# ModulePlatform.net
KiCad netlist of a schematic drawn in EAGLE
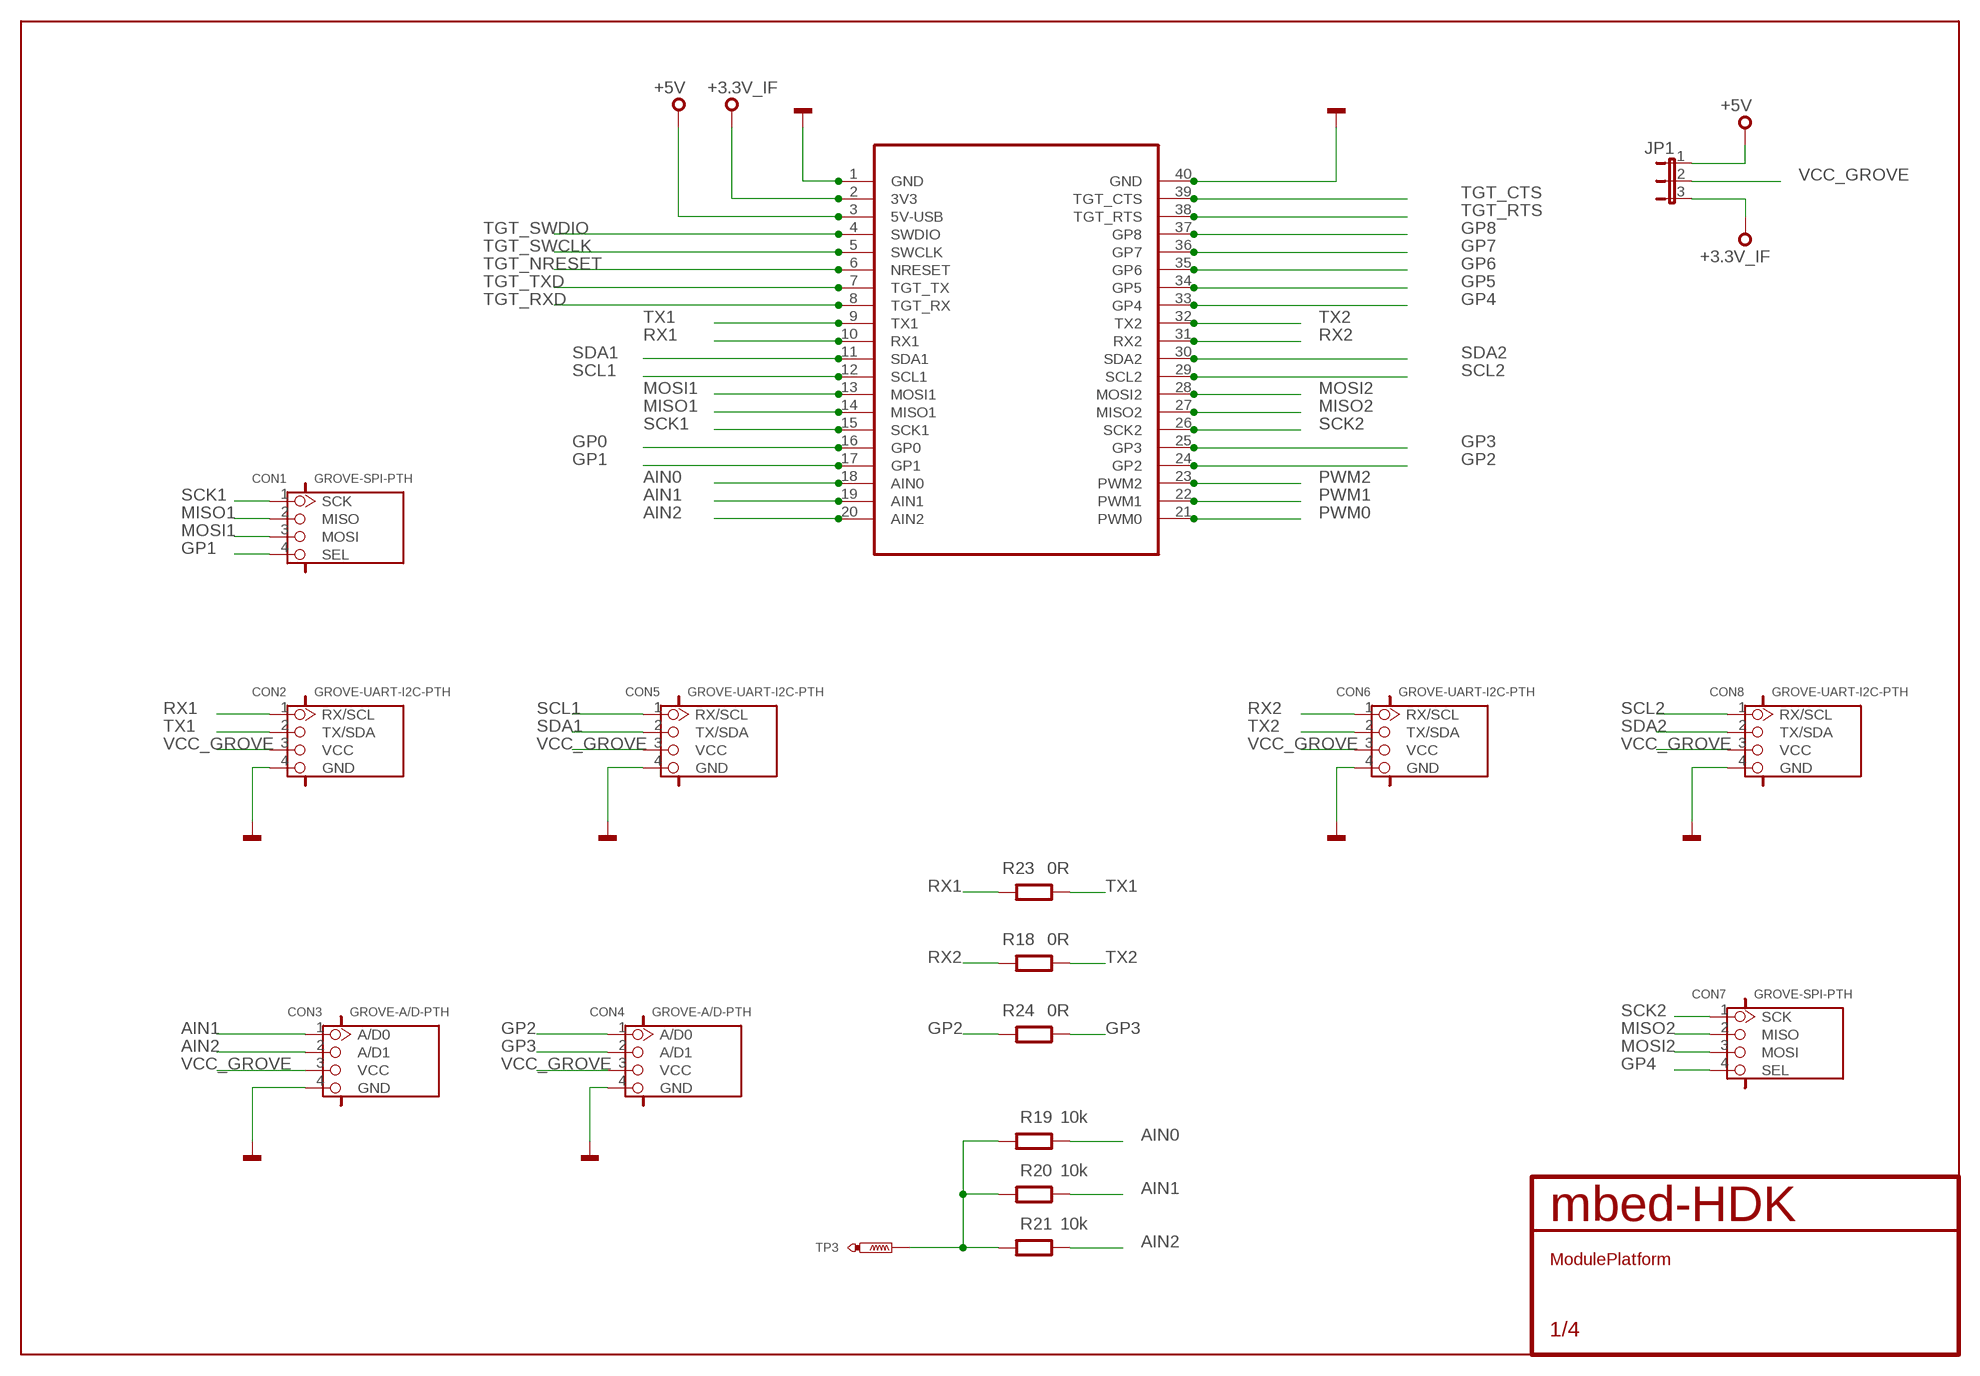
[diagram p0: schematic, sheet 1]
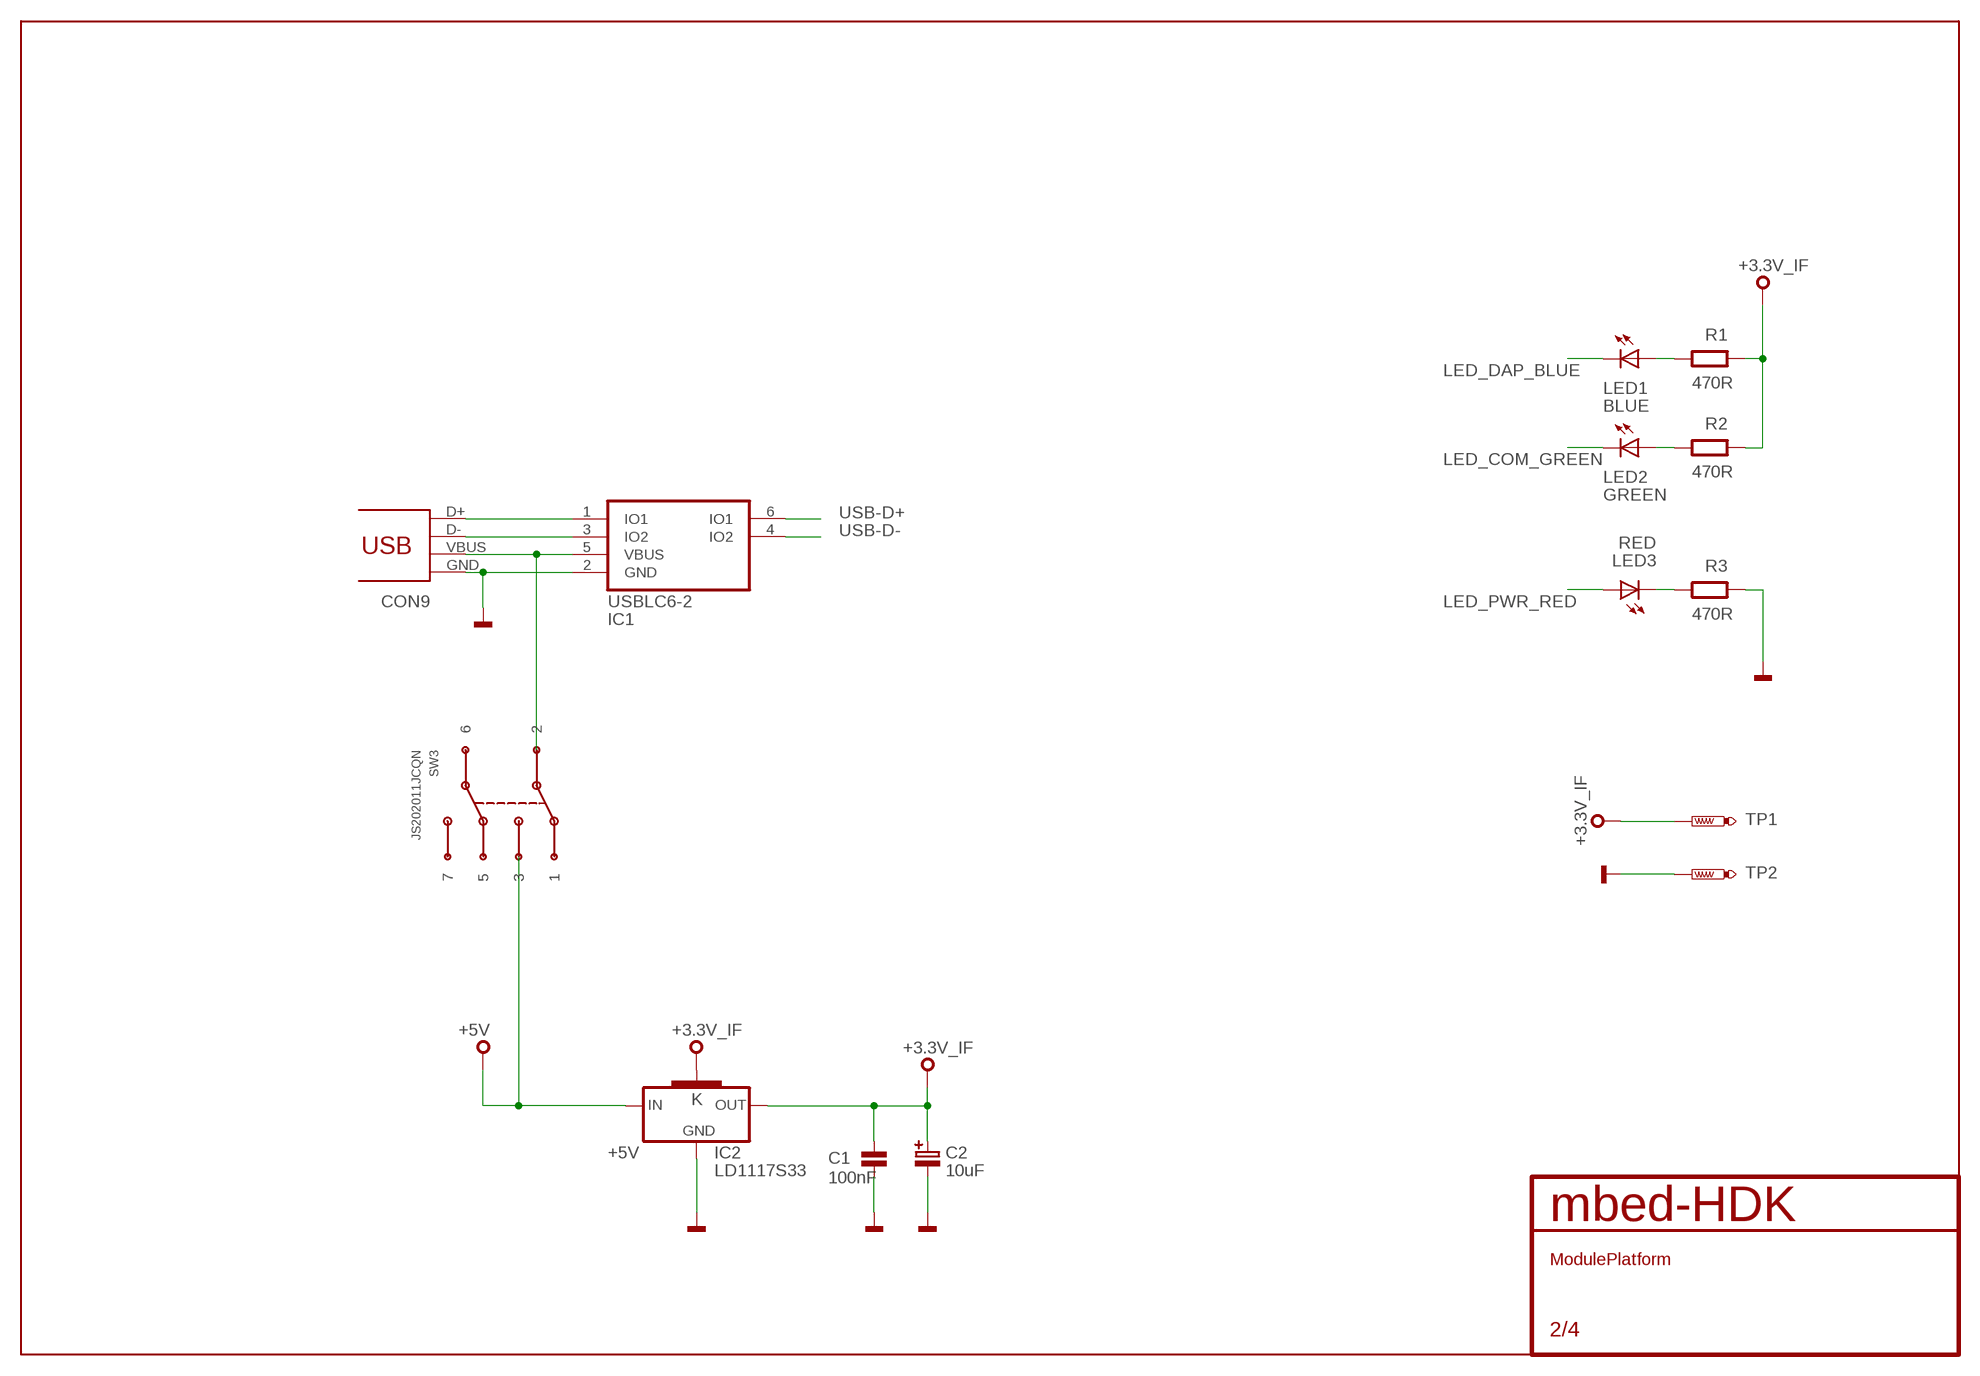
[diagram p1: schematic, sheet 2]
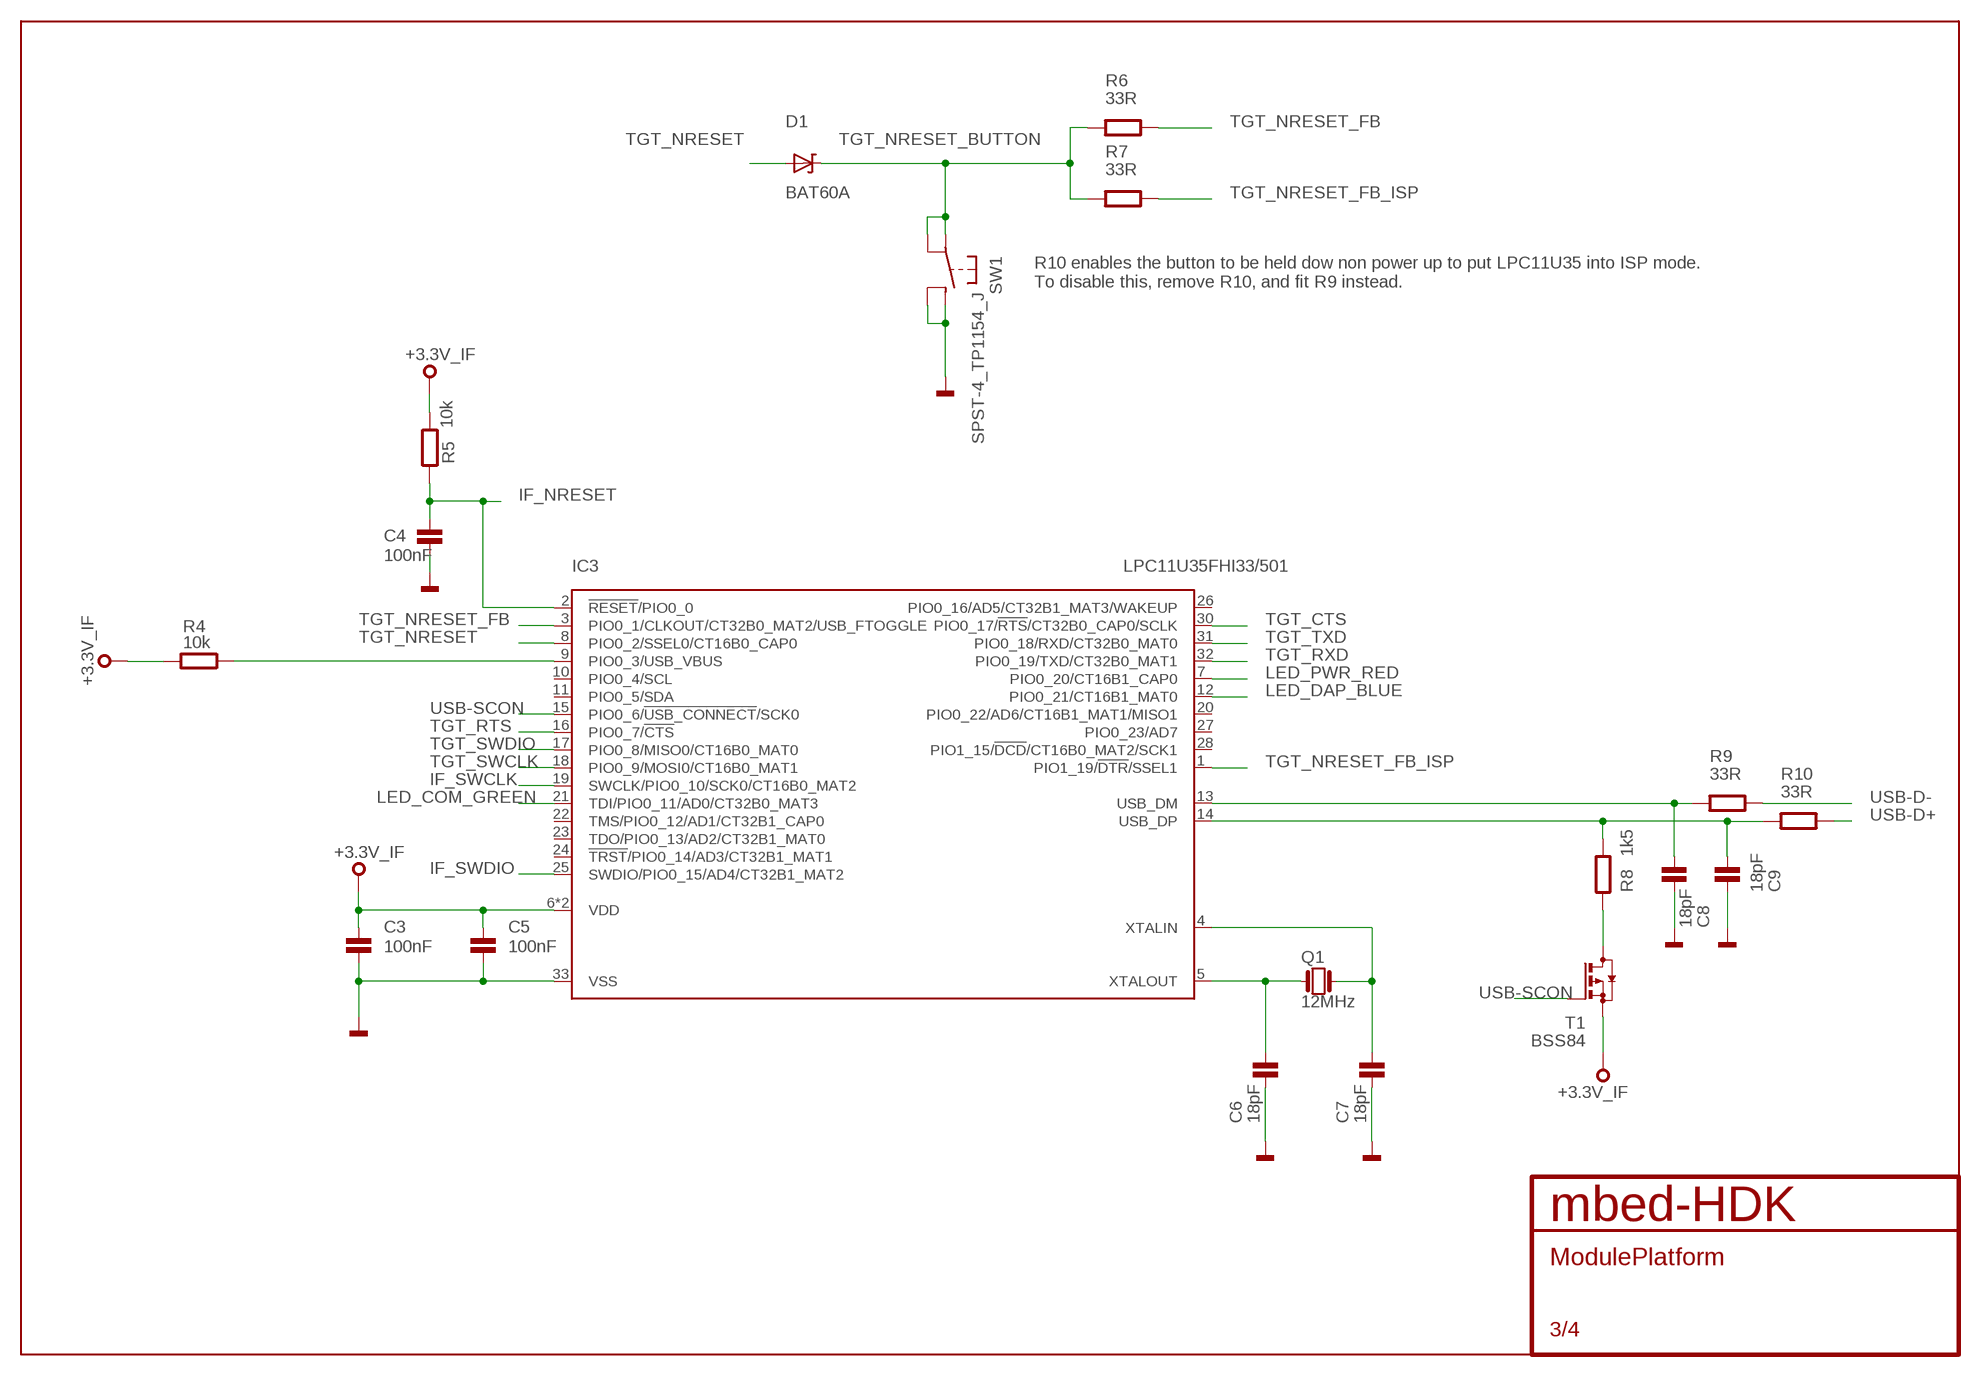
[diagram p2: schematic, sheet 3]
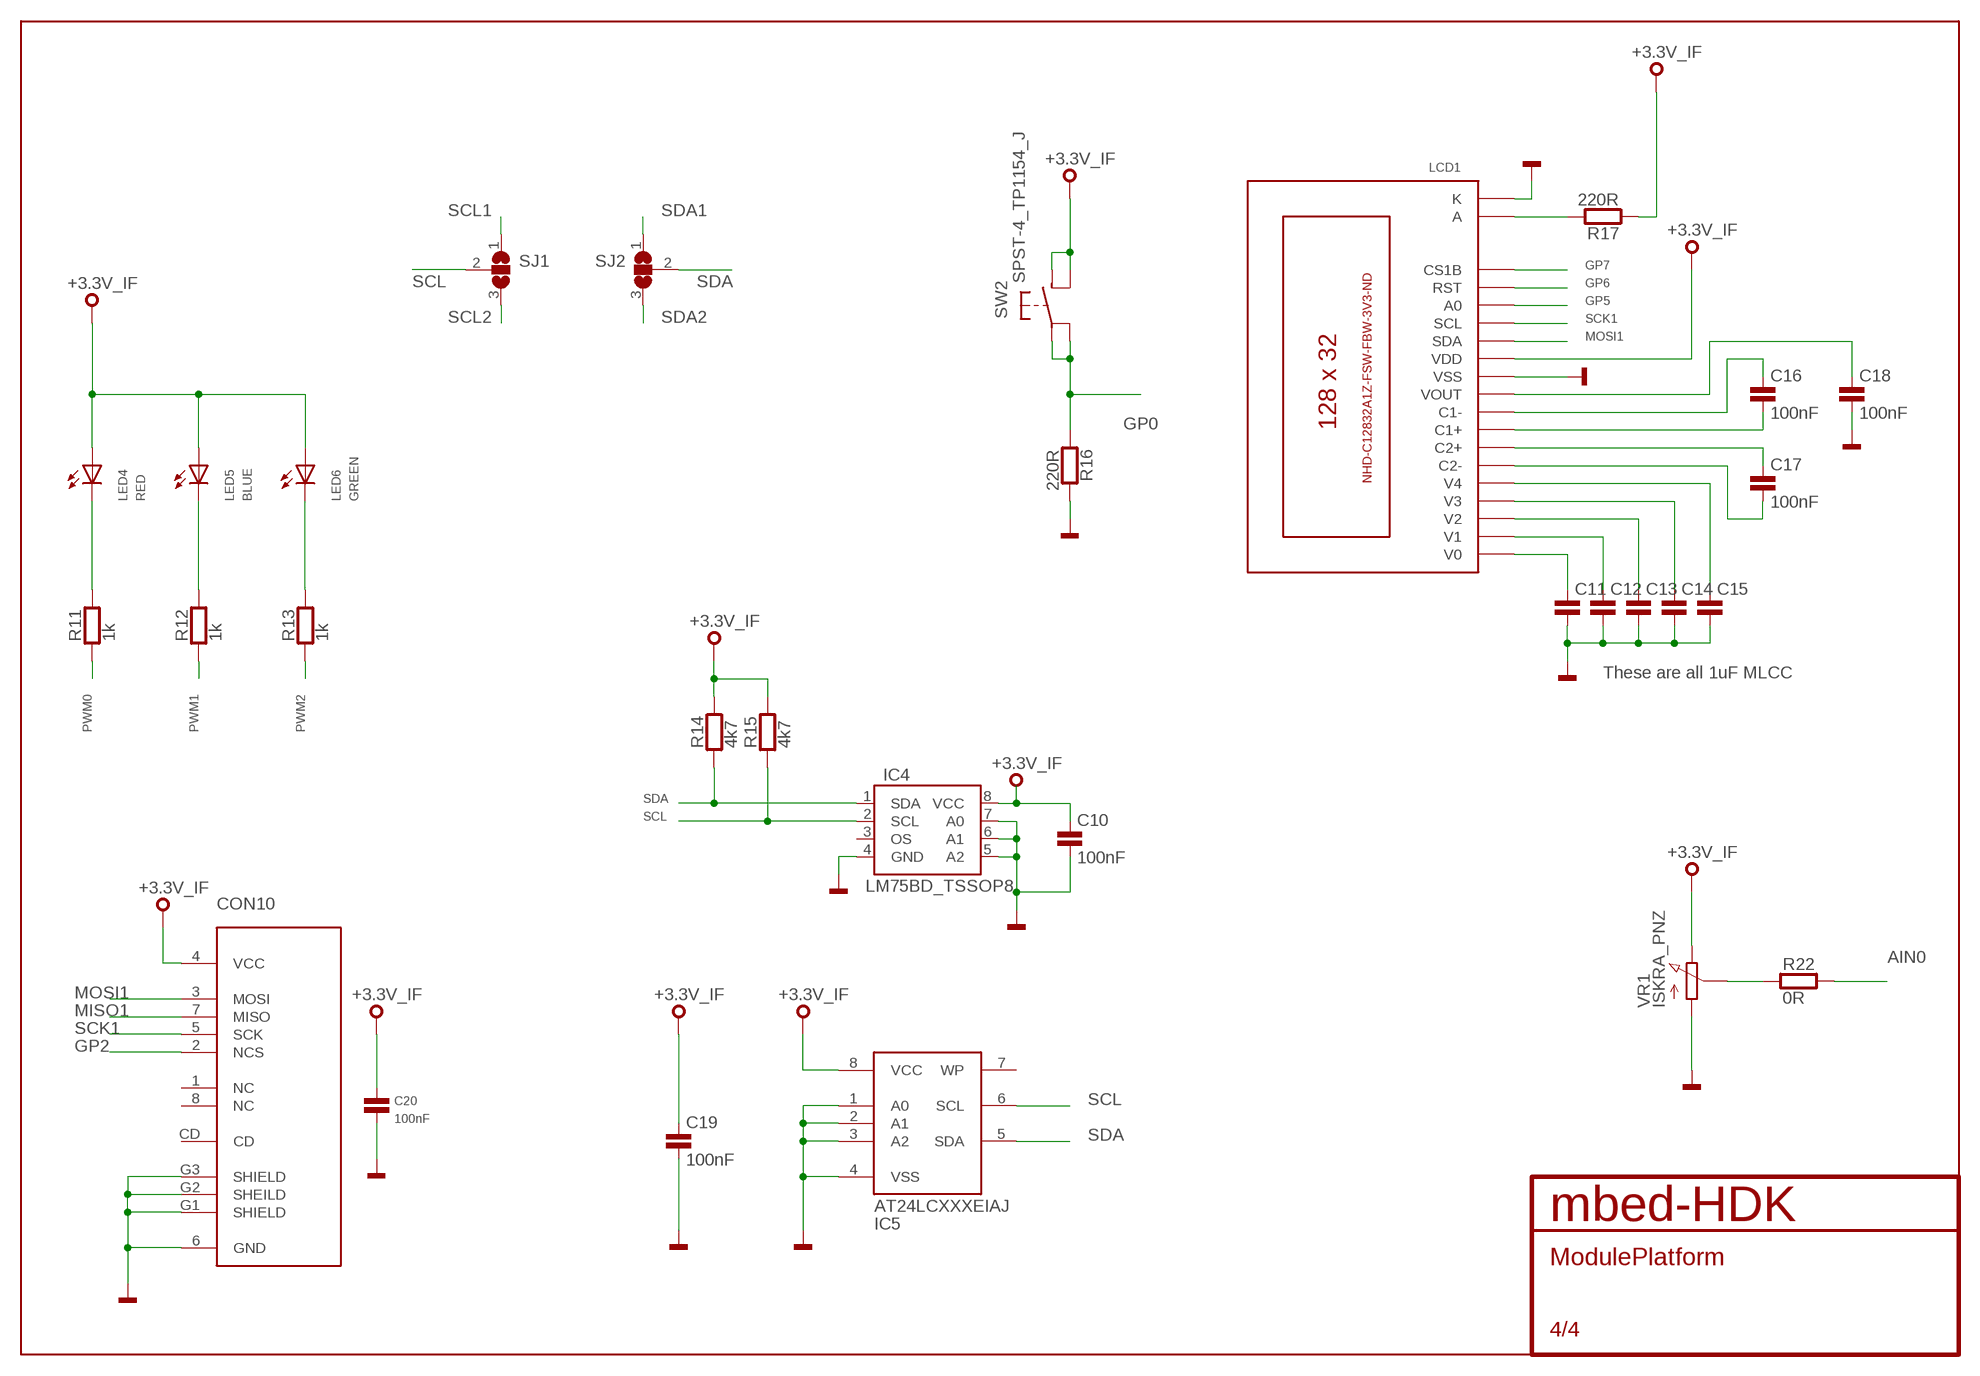
[diagram p3: schematic, sheet 4]

(export (version "E")
  (design (tool "Eeschema 10.0.6"))
  (components
    (comp (ref "C10")
      (value "100nF")
      (footprint "eagle-import:0603")
      (libsource (lib "eagle-import") (part "mbed-rlcq_C0603"))
    )
    (comp (ref "C11")
      (value "100nF")
      (footprint "eagle-import:0603")
      (libsource (lib "eagle-import") (part "mbed-rlcq_C0603"))
    )
    (comp (ref "C12")
      (value "100nF")
      (footprint "eagle-import:0603")
      (libsource (lib "eagle-import") (part "mbed-rlcq_C0603"))
    )
    (comp (ref "C13")
      (value "100nF")
      (footprint "eagle-import:0603")
      (libsource (lib "eagle-import") (part "mbed-rlcq_C0603"))
    )
    (comp (ref "C14")
      (value "100nF")
      (footprint "eagle-import:0603")
      (libsource (lib "eagle-import") (part "mbed-rlcq_C0603"))
    )
    (comp (ref "C15")
      (value "100nF")
      (footprint "eagle-import:0603")
      (libsource (lib "eagle-import") (part "mbed-rlcq_C0603"))
    )
    (comp (ref "C16")
      (value "100nF")
      (footprint "eagle-import:0603")
      (libsource (lib "eagle-import") (part "mbed-rlcq_C0603"))
    )
    (comp (ref "C17")
      (value "100nF")
      (footprint "eagle-import:0603")
      (libsource (lib "eagle-import") (part "mbed-rlcq_C0603"))
    )
    (comp (ref "C18")
      (value "100nF")
      (footprint "eagle-import:0603")
      (libsource (lib "eagle-import") (part "mbed-rlcq_C0603"))
    )
    (comp (ref "C19")
      (value "100nF")
      (footprint "eagle-import:0603")
      (libsource (lib "eagle-import") (part "mbed-rlcq_C0603"))
    )
    (comp (ref "C20")
      (value "100nF")
      (footprint "eagle-import:0603")
      (libsource (lib "eagle-import") (part "C0603"))
    )
    (comp (ref "CON10")
      (value "MICRO-SD")
      (footprint "eagle-import:AMPHENOL-101-00660-68-6")
      (libsource (lib "eagle-import") (part "MICRO-SD"))
    )
    (comp (ref "IC4")
      (value "LM75BD_TSSOP8")
      (footprint "eagle-import:TSSOP8")
      (libsource (lib "eagle-import") (part "LM75BD_TSSOP8"))
    )
    (comp (ref "IC5")
      (value "AT24LCXXXEIAJ")
      (footprint "eagle-import:SO08-EIAJ")
      (libsource (lib "eagle-import") (part "AT24LCXXXEIAJ"))
    )
    (comp (ref "LCD1")
      (value "C12832A1Z")
      (footprint "eagle-import:C12832A1Z")
      (libsource (lib "eagle-import") (part "C12832A1Z"))
    )
    (comp (ref "LED4")
      (value "RED")
      (footprint "eagle-import:CHIPLED_0603")
      (libsource (lib "eagle-import") (part "LED0603"))
    )
    (comp (ref "LED5")
      (value "BLUE")
      (footprint "eagle-import:CHIPLED_0603")
      (libsource (lib "eagle-import") (part "LED0603"))
    )
    (comp (ref "LED6")
      (value "GREEN")
      (footprint "eagle-import:CHIPLED_0603")
      (libsource (lib "eagle-import") (part "LED0603"))
    )
    (comp (ref "R11")
      (value "1k")
      (footprint "eagle-import:0603")
      (libsource (lib "eagle-import") (part "mbed-rlcq_R0603"))
    )
    (comp (ref "R12")
      (value "1k")
      (footprint "eagle-import:0603")
      (libsource (lib "eagle-import") (part "mbed-rlcq_R0603"))
    )
    (comp (ref "R13")
      (value "1k")
      (footprint "eagle-import:0603")
      (libsource (lib "eagle-import") (part "mbed-rlcq_R0603"))
    )
    (comp (ref "R14")
      (value "4k7")
      (footprint "eagle-import:0603")
      (libsource (lib "eagle-import") (part "mbed-rlcq_R0603"))
    )
    (comp (ref "R15")
      (value "4k7")
      (footprint "eagle-import:0603")
      (libsource (lib "eagle-import") (part "mbed-rlcq_R0603"))
    )
    (comp (ref "R16")
      (value "220R")
      (footprint "eagle-import:0603")
      (libsource (lib "eagle-import") (part "mbed-rlcq_R0603"))
    )
    (comp (ref "R17")
      (value "220R")
      (footprint "eagle-import:0603")
      (libsource (lib "eagle-import") (part "mbed-rlcq_R0603"))
    )
    (comp (ref "R22")
      (value "0R")
      (footprint "eagle-import:0603")
      (libsource (lib "eagle-import") (part "mbed-rlcq_R0603"))
    )
    (comp (ref "SJ1")
      (value "SJ2W")
      (footprint "eagle-import:SJ_2")
      (libsource (lib "eagle-import") (part "SJ2W"))
    )
    (comp (ref "SJ2")
      (value "SJ2W")
      (footprint "eagle-import:SJ_2")
      (libsource (lib "eagle-import") (part "SJ2W"))
    )
    (comp (ref "SW2")
      (value "SPST-4_TP1154_J")
      (footprint "eagle-import:TP-1154X")
      (libsource (lib "eagle-import") (part "SPST-4_TP1154_J"))
    )
    (comp (ref "VR1")
      (value "ISKRA_PNZ")
      (footprint "eagle-import:CA14V")
      (libsource (lib "eagle-import") (part "ISKRA_PNZ"))
    )
    (comp (ref "C3")
      (value "100nF")
      (footprint "eagle-import:0603")
      (libsource (lib "eagle-import") (part "C0603"))
    )
    (comp (ref "C4")
      (value "100nF")
      (footprint "eagle-import:0603")
      (libsource (lib "eagle-import") (part "C0603"))
    )
    (comp (ref "C5")
      (value "100nF")
      (footprint "eagle-import:0603")
      (libsource (lib "eagle-import") (part "C0603"))
    )
    (comp (ref "C6")
      (value "18pF")
      (footprint "eagle-import:0603")
      (libsource (lib "eagle-import") (part "C0603"))
    )
    (comp (ref "C7")
      (value "18pF")
      (footprint "eagle-import:0603")
      (libsource (lib "eagle-import") (part "C0603"))
    )
    (comp (ref "C8")
      (value "18pF")
      (footprint "eagle-import:0603")
      (libsource (lib "eagle-import") (part "C0603"))
    )
    (comp (ref "C9")
      (value "18pF")
      (footprint "eagle-import:0603")
      (libsource (lib "eagle-import") (part "C0603"))
    )
    (comp (ref "D1")
      (value "BAT60A")
      (footprint "eagle-import:BAT60A")
      (libsource (lib "eagle-import") (part "BAT60A"))
    )
    (comp (ref "IC3")
      (value "LPC11U35FHI33/501")
      (footprint "eagle-import:SOT617-3")
      (libsource (lib "eagle-import") (part "LPC11U35FHI33/501"))
    )
    (comp (ref "Q1")
      (value "12MHz")
      (footprint "eagle-import:3.2X.2.5")
      (libsource (lib "eagle-import") (part "Q_3.2X2.5"))
    )
    (comp (ref "R4")
      (value "10k")
      (footprint "eagle-import:0603@1")
      (libsource (lib "eagle-import") (part "R0603"))
    )
    (comp (ref "R5")
      (value "10k")
      (footprint "eagle-import:0603@1")
      (libsource (lib "eagle-import") (part "R0603"))
    )
    (comp (ref "R6")
      (value "33R")
      (footprint "eagle-import:0603@1")
      (libsource (lib "eagle-import") (part "R0603"))
    )
    (comp (ref "R7")
      (value "33R")
      (footprint "eagle-import:0603@1")
      (libsource (lib "eagle-import") (part "R0603"))
    )
    (comp (ref "R8")
      (value "1k5")
      (footprint "eagle-import:0603@1")
      (libsource (lib "eagle-import") (part "R0603"))
    )
    (comp (ref "R9")
      (value "33R")
      (footprint "eagle-import:0603@1")
      (libsource (lib "eagle-import") (part "R0603"))
    )
    (comp (ref "R10")
      (value "33R")
      (footprint "eagle-import:0603@1")
      (libsource (lib "eagle-import") (part "R0603"))
    )
    (comp (ref "SW1")
      (value "SPST-4_TP1154_J")
      (footprint "eagle-import:TP-1154X")
      (libsource (lib "eagle-import") (part "SPST-4_TP1154_J"))
    )
    (comp (ref "T1")
      (value "BSS84")
      (footprint "eagle-import:SOT23")
      (libsource (lib "eagle-import") (part "BSS84"))
    )
    (comp (ref "CON1")
      (value "GROVE-SPI-PTH")
      (footprint "eagle-import:HW4-2.0")
      (libsource (lib "eagle-import") (part "GROVE-SPI-PTH"))
    )
    (comp (ref "CON2")
      (value "GROVE-UART-I2C-PTH")
      (footprint "eagle-import:HW4-2.0")
      (libsource (lib "eagle-import") (part "GROVE-UART-I2C-PTH"))
    )
    (comp (ref "CON3")
      (value "GROVE-A/D-PTH")
      (footprint "eagle-import:HW4-2.0")
      (libsource (lib "eagle-import") (part "GROVE-A/D-PTH"))
    )
    (comp (ref "CON4")
      (value "GROVE-A/D-PTH")
      (footprint "eagle-import:HW4-2.0")
      (libsource (lib "eagle-import") (part "GROVE-A/D-PTH"))
    )
    (comp (ref "CON5")
      (value "GROVE-UART-I2C-PTH")
      (footprint "eagle-import:HW4-2.0")
      (libsource (lib "eagle-import") (part "GROVE-UART-I2C-PTH"))
    )
    (comp (ref "CON6")
      (value "GROVE-UART-I2C-PTH")
      (footprint "eagle-import:HW4-2.0")
      (libsource (lib "eagle-import") (part "GROVE-UART-I2C-PTH"))
    )
    (comp (ref "CON7")
      (value "GROVE-SPI-PTH")
      (footprint "eagle-import:HW4-2.0")
      (libsource (lib "eagle-import") (part "GROVE-SPI-PTH"))
    )
    (comp (ref "CON8")
      (value "GROVE-UART-I2C-PTH")
      (footprint "eagle-import:HW4-2.0")
      (libsource (lib "eagle-import") (part "GROVE-UART-I2C-PTH"))
    )
    (comp (ref "JP1")
      (value "JP2E")
      (footprint "eagle-import:JP2")
      (libsource (lib "eagle-import") (part "JP2E"))
    )
    (comp (ref "R18")
      (value "0R")
      (footprint "eagle-import:0603@1")
      (libsource (lib "eagle-import") (part "R0603"))
    )
    (comp (ref "R19")
      (value "10k")
      (footprint "eagle-import:0603@1")
      (libsource (lib "eagle-import") (part "R0603"))
    )
    (comp (ref "R20")
      (value "10k")
      (footprint "eagle-import:0603@1")
      (libsource (lib "eagle-import") (part "R0603"))
    )
    (comp (ref "R21")
      (value "10k")
      (footprint "eagle-import:0603@1")
      (libsource (lib "eagle-import") (part "R0603"))
    )
    (comp (ref "R23")
      (value "0R")
      (footprint "eagle-import:0603@1")
      (libsource (lib "eagle-import") (part "R0603"))
    )
    (comp (ref "R24")
      (value "0R")
      (footprint "eagle-import:0603@1")
      (libsource (lib "eagle-import") (part "R0603"))
    )
    (comp (ref "SKT1")
      (value "MODULE_SOCKET")
      (footprint "eagle-import:MODULE_SOCKET")
      (libsource (lib "eagle-import") (part "MODULE_SOCKET"))
    )
    (comp (ref "TP3")
      (value "TEST-POINT-50R-PTH")
      (footprint "eagle-import:TP50-PTH")
      (libsource (lib "eagle-import") (part "TEST-POINT-50R-PTH"))
    )
    (comp (ref "C1")
      (value "100nF")
      (footprint "eagle-import:0603")
      (libsource (lib "eagle-import") (part "C0603"))
    )
    (comp (ref "C2")
      (value "10uF")
      (footprint "eagle-import:SMC_B")
      (libsource (lib "eagle-import") (part "C-POLB"))
    )
    (comp (ref "CON9")
      (value "USB_MICROB")
      (footprint "eagle-import:MOLEX-47364-0001")
      (libsource (lib "eagle-import") (part "USB_MICROB"))
    )
    (comp (ref "IC1")
      (value "USBLC6-2SC6")
      (footprint "eagle-import:SOT23-6L")
      (libsource (lib "eagle-import") (part "USBLC6-2SC6"))
    )
    (comp (ref "IC2")
      (value "LD1117S33")
      (footprint "eagle-import:SOT223")
      (libsource (lib "eagle-import") (part "LD1117S33"))
    )
    (comp (ref "LED1")
      (value "BLUE")
      (footprint "eagle-import:CHIPLED_0603")
      (libsource (lib "eagle-import") (part "LED0603"))
    )
    (comp (ref "LED2")
      (value "GREEN")
      (footprint "eagle-import:CHIPLED_0603")
      (libsource (lib "eagle-import") (part "LED0603"))
    )
    (comp (ref "LED3")
      (value "RED")
      (footprint "eagle-import:CHIPLED_0603")
      (libsource (lib "eagle-import") (part "LED0603"))
    )
    (comp (ref "R1")
      (value "470R")
      (footprint "eagle-import:0603@1")
      (libsource (lib "eagle-import") (part "R0603"))
    )
    (comp (ref "R2")
      (value "470R")
      (footprint "eagle-import:0603@1")
      (libsource (lib "eagle-import") (part "R0603"))
    )
    (comp (ref "R3")
      (value "470R")
      (footprint "eagle-import:0603@1")
      (libsource (lib "eagle-import") (part "R0603"))
    )
    (comp (ref "SW3")
      (value "JS202011JCQN")
      (footprint "eagle-import:JS202011JCQN")
      (fields (field (name "MF") "C&K Components"))
      (libsource (lib "eagle-import") (part "JS202011JCQN"))
    )
    (comp (ref "TP1")
      (value "TEST-POINT-50R-PTH")
      (footprint "eagle-import:TP50-PTH")
      (libsource (lib "eagle-import") (part "TEST-POINT-50R-PTH"))
    )
    (comp (ref "TP2")
      (value "TEST-POINT-50R-PTH")
      (footprint "eagle-import:TP50-PTH")
      (libsource (lib "eagle-import") (part "TEST-POINT-50R-PTH"))
    )
  )
  (nets
    (net (code "1") (name "+3.3V_IF") (class "Default")
      (node (ref "C1") (pin "1") (pinfunction "P$1_1") (pintype "passive"))
      (node (ref "C10") (pin "1") (pinfunction "P$1_1") (pintype "passive"))
      (node (ref "C19") (pin "1") (pinfunction "P$1_1") (pintype "passive"))
      (node (ref "C2") (pin "+") (pinfunction "+_+") (pintype "passive"))
      (node (ref "C20") (pin "1") (pinfunction "P$1_1") (pintype "passive"))
      (node (ref "C3") (pin "1") (pinfunction "P$1_1") (pintype "passive"))
      (node (ref "C5") (pin "1") (pinfunction "P$1_1") (pintype "passive"))
      (node (ref "CON10") (pin "4") (pinfunction "VCC_4") (pintype "bidirectional"))
      (node (ref "IC2") (pin "2") (pinfunction "OUT_2") (pintype "passive"))
      (node (ref "IC2") (pin "4") (pinfunction "K_4") (pintype "passive"))
      (node (ref "IC3") (pin "29") (pinfunction "VDD_29") (pintype "passive"))
      (node (ref "IC3") (pin "6") (pinfunction "VDD_6") (pintype "passive"))
      (node (ref "IC4") (pin "8") (pinfunction "VCC_8") (pintype "bidirectional"))
      (node (ref "IC5") (pin "8") (pinfunction "VCC_8") (pintype "power_in"))
      (node (ref "JP1") (pin "3") (pinfunction "3_3") (pintype "passive"))
      (node (ref "LCD1") (pin "P$12") (pinfunction "VDD_P$12") (pintype "bidirectional"))
      (node (ref "LED4") (pin "A") (pinfunction "A_A") (pintype "passive"))
      (node (ref "LED5") (pin "A") (pinfunction "A_A") (pintype "passive"))
      (node (ref "LED6") (pin "A") (pinfunction "A_A") (pintype "passive"))
      (node (ref "R1") (pin "1") (pinfunction "P$1_1") (pintype "passive"))
      (node (ref "R14") (pin "2") (pinfunction "P$2_2") (pintype "passive"))
      (node (ref "R15") (pin "2") (pinfunction "P$2_2") (pintype "passive"))
      (node (ref "R17") (pin "1") (pinfunction "P$1_1") (pintype "passive"))
      (node (ref "R2") (pin "1") (pinfunction "P$1_1") (pintype "passive"))
      (node (ref "R4") (pin "2") (pinfunction "P$2_2") (pintype "passive"))
      (node (ref "R5") (pin "2") (pinfunction "P$2_2") (pintype "passive"))
      (node (ref "SKT1") (pin "2") (pinfunction "3V3_2") (pintype "bidirectional"))
      (node (ref "SKT1") (pin "P$42") (pinfunction "P$42_P$42") (pintype "bidirectional"))
      (node (ref "SW2") (pin "B1") (pinfunction "B1_B1") (pintype "passive"))
      (node (ref "SW2") (pin "B2") (pinfunction "B2_B2") (pintype "passive"))
      (node (ref "T1") (pin "2") (pinfunction "S_2") (pintype "passive"))
      (node (ref "TP1") (pin "TP") (pinfunction "TP_TP") (pintype "input"))
      (node (ref "VR1") (pin "P$3") (pinfunction "E_P$3") (pintype "passive"))
    )
    (net (code "2") (name "+5V") (class "Default")
      (node (ref "IC2") (pin "3") (pinfunction "IN_3") (pintype "input"))
      (node (ref "JP1") (pin "1") (pinfunction "1_1") (pintype "passive"))
      (node (ref "SKT1") (pin "3") (pinfunction "5V-USB_3") (pintype "bidirectional"))
      (node (ref "SKT1") (pin "P$43") (pinfunction "P$43_P$43") (pintype "bidirectional"))
      (node (ref "SW3") (pin "3") (pinfunction "3_3") (pintype "bidirectional"))
    )
    (net (code "3") (name "AIN0") (class "Default")
      (node (ref "R19") (pin "1") (pinfunction "P$1_1") (pintype "passive"))
      (node (ref "R22") (pin "2") (pinfunction "P$2_2") (pintype "passive"))
      (node (ref "SKT1") (pin "18") (pinfunction "AIN0_18") (pintype "bidirectional"))
      (node (ref "SKT1") (pin "P$58") (pinfunction "P$58_P$58") (pintype "bidirectional"))
    )
    (net (code "4") (name "AIN1") (class "Default")
      (node (ref "CON3") (pin "1") (pinfunction "A/D0_1") (pintype "bidirectional"))
      (node (ref "R20") (pin "1") (pinfunction "P$1_1") (pintype "passive"))
      (node (ref "SKT1") (pin "19") (pinfunction "AIN1_19") (pintype "bidirectional"))
      (node (ref "SKT1") (pin "P$59") (pinfunction "P$59_P$59") (pintype "bidirectional"))
    )
    (net (code "5") (name "AIN2") (class "Default")
      (node (ref "CON3") (pin "2") (pinfunction "A/D1_2") (pintype "bidirectional"))
      (node (ref "R21") (pin "1") (pinfunction "P$1_1") (pintype "passive"))
      (node (ref "SKT1") (pin "20") (pinfunction "AIN2_20") (pintype "bidirectional"))
      (node (ref "SKT1") (pin "P$60") (pinfunction "P$60_P$60") (pintype "bidirectional"))
    )
    (net (code "6") (name "GND") (class "Default")
      (node (ref "C1") (pin "2") (pinfunction "P$2_2") (pintype "passive"))
      (node (ref "C10") (pin "2") (pinfunction "P$2_2") (pintype "passive"))
      (node (ref "C11") (pin "2") (pinfunction "P$2_2") (pintype "passive"))
      (node (ref "C12") (pin "2") (pinfunction "P$2_2") (pintype "passive"))
      (node (ref "C13") (pin "2") (pinfunction "P$2_2") (pintype "passive"))
      (node (ref "C14") (pin "2") (pinfunction "P$2_2") (pintype "passive"))
      (node (ref "C15") (pin "2") (pinfunction "P$2_2") (pintype "passive"))
      (node (ref "C18") (pin "2") (pinfunction "P$2_2") (pintype "passive"))
      (node (ref "C19") (pin "2") (pinfunction "P$2_2") (pintype "passive"))
      (node (ref "C2") (pin "-") (pinfunction "-_-") (pintype "passive"))
      (node (ref "C20") (pin "2") (pinfunction "P$2_2") (pintype "passive"))
      (node (ref "C3") (pin "2") (pinfunction "P$2_2") (pintype "passive"))
      (node (ref "C4") (pin "2") (pinfunction "P$2_2") (pintype "passive"))
      (node (ref "C5") (pin "2") (pinfunction "P$2_2") (pintype "passive"))
      (node (ref "C6") (pin "2") (pinfunction "P$2_2") (pintype "passive"))
      (node (ref "C7") (pin "2") (pinfunction "P$2_2") (pintype "passive"))
      (node (ref "C8") (pin "2") (pinfunction "P$2_2") (pintype "passive"))
      (node (ref "C9") (pin "2") (pinfunction "P$2_2") (pintype "passive"))
      (node (ref "CON10") (pin "6") (pinfunction "GND_6") (pintype "bidirectional"))
      (node (ref "CON10") (pin "G1") (pinfunction "SHIELD_G1") (pintype "bidirectional"))
      (node (ref "CON10") (pin "G2") (pinfunction "SHEILD_G2") (pintype "bidirectional"))
      (node (ref "CON10") (pin "G3") (pinfunction "SHIELD_G3") (pintype "bidirectional"))
      (node (ref "CON2") (pin "4") (pinfunction "GND_4") (pintype "bidirectional"))
      (node (ref "CON3") (pin "4") (pinfunction "GND_4") (pintype "bidirectional"))
      (node (ref "CON4") (pin "4") (pinfunction "GND_4") (pintype "bidirectional"))
      (node (ref "CON5") (pin "4") (pinfunction "GND_4") (pintype "bidirectional"))
      (node (ref "CON6") (pin "4") (pinfunction "GND_4") (pintype "bidirectional"))
      (node (ref "CON8") (pin "4") (pinfunction "GND_4") (pintype "bidirectional"))
      (node (ref "CON9") (pin "GND") (pinfunction "GND_GND") (pintype "bidirectional"))
      (node (ref "IC1") (pin "2") (pinfunction "GND_2") (pintype "bidirectional"))
      (node (ref "IC2") (pin "1") (pinfunction "GND_1") (pintype "input"))
      (node (ref "IC3") (pin "33") (pinfunction "VSS_33") (pintype "passive"))
      (node (ref "IC4") (pin "4") (pinfunction "GND_4") (pintype "bidirectional"))
      (node (ref "IC4") (pin "5") (pinfunction "A2_5") (pintype "bidirectional"))
      (node (ref "IC4") (pin "6") (pinfunction "A1_6") (pintype "bidirectional"))
      (node (ref "IC4") (pin "7") (pinfunction "A0_7") (pintype "bidirectional"))
      (node (ref "IC5") (pin "1") (pinfunction "A0_1") (pintype "bidirectional"))
      (node (ref "IC5") (pin "2") (pinfunction "A1_2") (pintype "bidirectional"))
      (node (ref "IC5") (pin "3") (pinfunction "A2_3") (pintype "bidirectional"))
      (node (ref "IC5") (pin "4") (pinfunction "VSS_4") (pintype "power_in"))
      (node (ref "LCD1") (pin "K") (pinfunction "K_K") (pintype "bidirectional"))
      (node (ref "LCD1") (pin "P$11") (pinfunction "VSS_P$11") (pintype "bidirectional"))
      (node (ref "R16") (pin "2") (pinfunction "P$2_2") (pintype "passive"))
      (node (ref "R3") (pin "1") (pinfunction "P$1_1") (pintype "passive"))
      (node (ref "SKT1") (pin "1") (pinfunction "GND_1") (pintype "bidirectional"))
      (node (ref "SKT1") (pin "40") (pinfunction "GND_40") (pintype "bidirectional"))
      (node (ref "SKT1") (pin "P$41") (pinfunction "P$41_P$41") (pintype "bidirectional"))
      (node (ref "SKT1") (pin "P$80") (pinfunction "P$80_P$80") (pintype "bidirectional"))
      (node (ref "SW1") (pin "B1") (pinfunction "B1_B1") (pintype "passive"))
      (node (ref "SW1") (pin "B2") (pinfunction "B2_B2") (pintype "passive"))
      (node (ref "TP2") (pin "TP") (pinfunction "TP_TP") (pintype "input"))
      (node (ref "VR1") (pin "P$1") (pinfunction "A_P$1") (pintype "passive"))
    )
    (net (code "7") (name "GP0") (class "Default")
      (node (ref "R16") (pin "1") (pinfunction "P$1_1") (pintype "passive"))
      (node (ref "SKT1") (pin "16") (pinfunction "GP0_16") (pintype "bidirectional"))
      (node (ref "SKT1") (pin "P$56") (pinfunction "P$56_P$56") (pintype "bidirectional"))
      (node (ref "SW2") (pin "A1") (pinfunction "A1_A1") (pintype "passive"))
      (node (ref "SW2") (pin "A2") (pinfunction "A2_A2") (pintype "passive"))
    )
    (net (code "8") (name "GP1") (class "Default")
      (node (ref "CON1") (pin "4") (pinfunction "SEL_4") (pintype "bidirectional"))
      (node (ref "SKT1") (pin "17") (pinfunction "GP1_17") (pintype "bidirectional"))
      (node (ref "SKT1") (pin "P$57") (pinfunction "P$57_P$57") (pintype "bidirectional"))
    )
    (net (code "9") (name "GP2") (class "Default")
      (node (ref "CON10") (pin "2") (pinfunction "NCS_2") (pintype "bidirectional"))
      (node (ref "CON4") (pin "1") (pinfunction "A/D0_1") (pintype "bidirectional"))
      (node (ref "R24") (pin "2") (pinfunction "P$2_2") (pintype "passive"))
      (node (ref "SKT1") (pin "24") (pinfunction "GP2_24") (pintype "bidirectional"))
      (node (ref "SKT1") (pin "P$64") (pinfunction "P$64_P$64") (pintype "bidirectional"))
    )
    (net (code "10") (name "GP3") (class "Default")
      (node (ref "CON4") (pin "2") (pinfunction "A/D1_2") (pintype "bidirectional"))
      (node (ref "R24") (pin "1") (pinfunction "P$1_1") (pintype "passive"))
      (node (ref "SKT1") (pin "25") (pinfunction "GP3_25") (pintype "bidirectional"))
      (node (ref "SKT1") (pin "P$65") (pinfunction "P$65_P$65") (pintype "bidirectional"))
    )
    (net (code "11") (name "GP4") (class "Default")
      (node (ref "CON7") (pin "4") (pinfunction "SEL_4") (pintype "bidirectional"))
      (node (ref "SKT1") (pin "33") (pinfunction "GP4_33") (pintype "bidirectional"))
      (node (ref "SKT1") (pin "P$73") (pinfunction "P$73_P$73") (pintype "bidirectional"))
    )
    (net (code "12") (name "GP5") (class "Default")
      (node (ref "LCD1") (pin "P$15") (pinfunction "A0_P$15") (pintype "bidirectional"))
      (node (ref "SKT1") (pin "34") (pinfunction "GP5_34") (pintype "bidirectional"))
      (node (ref "SKT1") (pin "P$74") (pinfunction "P$74_P$74") (pintype "bidirectional"))
    )
    (net (code "13") (name "GP6") (class "Default")
      (node (ref "LCD1") (pin "P$16") (pinfunction "RST_P$16") (pintype "bidirectional"))
      (node (ref "SKT1") (pin "35") (pinfunction "GP6_35") (pintype "bidirectional"))
      (node (ref "SKT1") (pin "P$75") (pinfunction "P$75_P$75") (pintype "bidirectional"))
    )
    (net (code "14") (name "GP7") (class "Default")
      (node (ref "LCD1") (pin "P$17") (pinfunction "CS1B_P$17") (pintype "bidirectional"))
      (node (ref "SKT1") (pin "36") (pinfunction "GP7_36") (pintype "bidirectional"))
      (node (ref "SKT1") (pin "P$76") (pinfunction "P$76_P$76") (pintype "bidirectional"))
    )
    (net (code "15") (name "GP8") (class "Default")
      (node (ref "SKT1") (pin "37") (pinfunction "GP8_37") (pintype "bidirectional"))
      (node (ref "SKT1") (pin "P$77") (pinfunction "P$77_P$77") (pintype "bidirectional"))
    )
    (net (code "16") (name "IF_NRESET") (class "Default")
      (node (ref "C4") (pin "1") (pinfunction "P$1_1") (pintype "passive"))
      (node (ref "IC3") (pin "2") (pinfunction "~{RESET}/PIO0_0_2") (pintype "bidirectional"))
      (node (ref "R5") (pin "1") (pinfunction "P$1_1") (pintype "passive"))
    )
    (net (code "17") (name "IF_SWCLK") (class "Default")
      (node (ref "IC3") (pin "19") (pinfunction "SWCLK/PIO0_10/SCK0/CT16B0_MAT2_19") (pintype "bidirectional"))
    )
    (net (code "18") (name "IF_SWDIO") (class "Default")
      (node (ref "IC3") (pin "25") (pinfunction "SWDIO/PIO0_15/AD4/CT32B1_MAT2_25") (pintype "bidirectional"))
    )
    (net (code "19") (name "LED_COM_GREEN") (class "Default")
      (node (ref "IC3") (pin "21") (pinfunction "TDI/PIO0_11/AD0/CT32B0_MAT3_21") (pintype "bidirectional"))
      (node (ref "LED2") (pin "C") (pinfunction "C_C") (pintype "passive"))
    )
    (net (code "20") (name "LED_DAP_BLUE") (class "Default")
      (node (ref "IC3") (pin "12") (pinfunction "PIO0_21/CT16B1_MAT0_12") (pintype "bidirectional"))
      (node (ref "LED1") (pin "C") (pinfunction "C_C") (pintype "passive"))
    )
    (net (code "21") (name "LED_PWR_RED") (class "Default")
      (node (ref "IC3") (pin "7") (pinfunction "PIO0_20/CT16B1_CAP0_7") (pintype "bidirectional"))
      (node (ref "LED3") (pin "A") (pinfunction "A_A") (pintype "passive"))
    )
    (net (code "22") (name "MISO1") (class "Default")
      (node (ref "CON1") (pin "2") (pinfunction "MISO_2") (pintype "bidirectional"))
      (node (ref "CON10") (pin "7") (pinfunction "MISO_7") (pintype "bidirectional"))
      (node (ref "SKT1") (pin "14") (pinfunction "MISO1_14") (pintype "bidirectional"))
      (node (ref "SKT1") (pin "P$54") (pinfunction "P$54_P$54") (pintype "bidirectional"))
    )
    (net (code "23") (name "MISO2") (class "Default")
      (node (ref "CON7") (pin "2") (pinfunction "MISO_2") (pintype "bidirectional"))
      (node (ref "SKT1") (pin "27") (pinfunction "MISO2_27") (pintype "bidirectional"))
      (node (ref "SKT1") (pin "P$67") (pinfunction "P$67_P$67") (pintype "bidirectional"))
    )
    (net (code "24") (name "MOSI1") (class "Default")
      (node (ref "CON1") (pin "3") (pinfunction "MOSI_3") (pintype "bidirectional"))
      (node (ref "CON10") (pin "3") (pinfunction "MOSI_3") (pintype "bidirectional"))
      (node (ref "LCD1") (pin "P$13") (pinfunction "SDA_P$13") (pintype "bidirectional"))
      (node (ref "SKT1") (pin "13") (pinfunction "MOSI1_13") (pintype "bidirectional"))
      (node (ref "SKT1") (pin "P$53") (pinfunction "P$53_P$53") (pintype "bidirectional"))
    )
    (net (code "25") (name "MOSI2") (class "Default")
      (node (ref "CON7") (pin "3") (pinfunction "MOSI_3") (pintype "bidirectional"))
      (node (ref "SKT1") (pin "28") (pinfunction "MOSI2_28") (pintype "bidirectional"))
      (node (ref "SKT1") (pin "P$68") (pinfunction "P$68_P$68") (pintype "bidirectional"))
    )
    (net (code "26") (name "Net-(C6-P$1)") (class "Default")
      (node (ref "C6") (pin "1") (pinfunction "P$1_1") (pintype "passive"))
      (node (ref "IC3") (pin "5") (pinfunction "XTALOUT_5") (pintype "output"))
      (node (ref "Q1") (pin "P$1") (pinfunction "1_P$1") (pintype "passive"))
    )
    (net (code "27") (name "Net-(C7-P$1)") (class "Default")
      (node (ref "C7") (pin "1") (pinfunction "P$1_1") (pintype "passive"))
      (node (ref "IC3") (pin "4") (pinfunction "XTALIN_4") (pintype "input"))
      (node (ref "Q1") (pin "P$3") (pinfunction "2_P$3") (pintype "passive"))
    )
    (net (code "28") (name "Net-(C8-P$1)") (class "Default")
      (node (ref "C8") (pin "1") (pinfunction "P$1_1") (pintype "passive"))
      (node (ref "IC3") (pin "13") (pinfunction "USB_DM_13") (pintype "bidirectional"))
      (node (ref "R9") (pin "2") (pinfunction "P$2_2") (pintype "passive"))
    )
    (net (code "29") (name "Net-(C9-P$1)") (class "Default")
      (node (ref "C9") (pin "1") (pinfunction "P$1_1") (pintype "passive"))
      (node (ref "IC3") (pin "14") (pinfunction "USB_DP_14") (pintype "bidirectional"))
      (node (ref "R10") (pin "2") (pinfunction "P$2_2") (pintype "passive"))
      (node (ref "R8") (pin "2") (pinfunction "P$2_2") (pintype "passive"))
    )
    (net (code "30") (name "Net-(C11-P$1)") (class "Default")
      (node (ref "C11") (pin "1") (pinfunction "P$1_1") (pintype "passive"))
      (node (ref "LCD1") (pin "P$1") (pinfunction "V0_P$1") (pintype "bidirectional"))
    )
    (net (code "31") (name "Net-(C12-P$1)") (class "Default")
      (node (ref "C12") (pin "1") (pinfunction "P$1_1") (pintype "passive"))
      (node (ref "LCD1") (pin "P$2") (pinfunction "V1_P$2") (pintype "bidirectional"))
    )
    (net (code "32") (name "Net-(C13-P$1)") (class "Default")
      (node (ref "C13") (pin "1") (pinfunction "P$1_1") (pintype "passive"))
      (node (ref "LCD1") (pin "P$3") (pinfunction "V2_P$3") (pintype "bidirectional"))
    )
    (net (code "33") (name "Net-(C14-P$1)") (class "Default")
      (node (ref "C14") (pin "1") (pinfunction "P$1_1") (pintype "passive"))
      (node (ref "LCD1") (pin "P$4") (pinfunction "V3_P$4") (pintype "bidirectional"))
    )
    (net (code "34") (name "Net-(C15-P$1)") (class "Default")
      (node (ref "C15") (pin "1") (pinfunction "P$1_1") (pintype "passive"))
      (node (ref "LCD1") (pin "P$5") (pinfunction "V4_P$5") (pintype "bidirectional"))
    )
    (net (code "35") (name "Net-(C16-P$1)") (class "Default")
      (node (ref "C16") (pin "1") (pinfunction "P$1_1") (pintype "passive"))
      (node (ref "LCD1") (pin "P$9") (pinfunction "C1-_P$9") (pintype "bidirectional"))
    )
    (net (code "36") (name "Net-(C16-P$2)") (class "Default")
      (node (ref "C16") (pin "2") (pinfunction "P$2_2") (pintype "passive"))
      (node (ref "LCD1") (pin "P$8") (pinfunction "C1+_P$8") (pintype "bidirectional"))
    )
    (net (code "37") (name "Net-(C17-P$1)") (class "Default")
      (node (ref "C17") (pin "1") (pinfunction "P$1_1") (pintype "passive"))
      (node (ref "LCD1") (pin "P$7") (pinfunction "C2+_P$7") (pintype "bidirectional"))
    )
    (net (code "38") (name "Net-(C17-P$2)") (class "Default")
      (node (ref "C17") (pin "2") (pinfunction "P$2_2") (pintype "passive"))
      (node (ref "LCD1") (pin "P$6") (pinfunction "C2-_P$6") (pintype "bidirectional"))
    )
    (net (code "39") (name "Net-(C18-P$1)") (class "Default")
      (node (ref "C18") (pin "1") (pinfunction "P$1_1") (pintype "passive"))
      (node (ref "LCD1") (pin "P$10") (pinfunction "VOUT_P$10") (pintype "bidirectional"))
    )
    (net (code "40") (name "Net-(CON9-PadD+)") (class "Default")
      (node (ref "CON9") (pin "D+") (pinfunction "D+_D+") (pintype "bidirectional"))
      (node (ref "IC1") (pin "1") (pinfunction "IO1_1") (pintype "bidirectional"))
    )
    (net (code "41") (name "Net-(CON9-PadD-)") (class "Default")
      (node (ref "CON9") (pin "D-") (pinfunction "D-_D-") (pintype "bidirectional"))
      (node (ref "IC1") (pin "3") (pinfunction "IO2_3") (pintype "bidirectional"))
    )
    (net (code "42") (name "Net-(IC1-VBUS)") (class "Default")
      (node (ref "CON9") (pin "VBUS") (pinfunction "VBUS_VBUS") (pintype "bidirectional"))
      (node (ref "IC1") (pin "5") (pinfunction "VBUS_5") (pintype "bidirectional"))
      (node (ref "SW3") (pin "2") (pinfunction "2_2") (pintype "bidirectional"))
    )
    (net (code "43") (name "Net-(IC3-PIO0_3{slash}USB_VBUS)") (class "Default")
      (node (ref "IC3") (pin "9") (pinfunction "PIO0_3/USB_VBUS_9") (pintype "bidirectional"))
      (node (ref "R4") (pin "1") (pinfunction "P$1_1") (pintype "passive"))
    )
    (net (code "44") (name "Net-(R1-P$2)") (class "Default")
      (node (ref "LED1") (pin "A") (pinfunction "A_A") (pintype "passive"))
      (node (ref "R1") (pin "2") (pinfunction "P$2_2") (pintype "passive"))
    )
    (net (code "45") (name "Net-(R2-P$2)") (class "Default")
      (node (ref "LED2") (pin "A") (pinfunction "A_A") (pintype "passive"))
      (node (ref "R2") (pin "2") (pinfunction "P$2_2") (pintype "passive"))
    )
    (net (code "46") (name "Net-(R3-P$2)") (class "Default")
      (node (ref "LED3") (pin "C") (pinfunction "C_C") (pintype "passive"))
      (node (ref "R3") (pin "2") (pinfunction "P$2_2") (pintype "passive"))
    )
    (net (code "47") (name "Net-(R8-P$1)") (class "Default")
      (node (ref "R8") (pin "1") (pinfunction "P$1_1") (pintype "passive"))
      (node (ref "T1") (pin "3") (pinfunction "D_3") (pintype "passive"))
    )
    (net (code "48") (name "Net-(R11-P$2)") (class "Default")
      (node (ref "LED4") (pin "C") (pinfunction "C_C") (pintype "passive"))
      (node (ref "R11") (pin "2") (pinfunction "P$2_2") (pintype "passive"))
    )
    (net (code "49") (name "Net-(R12-P$2)") (class "Default")
      (node (ref "LED5") (pin "C") (pinfunction "C_C") (pintype "passive"))
      (node (ref "R12") (pin "2") (pinfunction "P$2_2") (pintype "passive"))
    )
    (net (code "50") (name "Net-(R13-P$2)") (class "Default")
      (node (ref "LED6") (pin "C") (pinfunction "C_C") (pintype "passive"))
      (node (ref "R13") (pin "2") (pinfunction "P$2_2") (pintype "passive"))
    )
    (net (code "51") (name "Net-(R17-P$2)") (class "Default")
      (node (ref "LCD1") (pin "A") (pinfunction "A_A") (pintype "bidirectional"))
      (node (ref "R17") (pin "2") (pinfunction "P$2_2") (pintype "passive"))
    )
    (net (code "52") (name "Net-(R19-P$2)") (class "Default")
      (node (ref "R19") (pin "2") (pinfunction "P$2_2") (pintype "passive"))
      (node (ref "R20") (pin "2") (pinfunction "P$2_2") (pintype "passive"))
      (node (ref "R21") (pin "2") (pinfunction "P$2_2") (pintype "passive"))
      (node (ref "TP3") (pin "TP") (pinfunction "TP_TP") (pintype "input"))
    )
    (net (code "53") (name "Net-(R22-P$1)") (class "Default")
      (node (ref "R22") (pin "1") (pinfunction "P$1_1") (pintype "passive"))
      (node (ref "VR1") (pin "P$2") (pinfunction "S_P$2") (pintype "passive"))
    )
    (net (code "54") (name "PWM0") (class "Default")
      (node (ref "R11") (pin "1") (pinfunction "P$1_1") (pintype "passive"))
      (node (ref "SKT1") (pin "21") (pinfunction "PWM0_21") (pintype "bidirectional"))
      (node (ref "SKT1") (pin "P$61") (pinfunction "P$61_P$61") (pintype "bidirectional"))
    )
    (net (code "55") (name "PWM1") (class "Default")
      (node (ref "R12") (pin "1") (pinfunction "P$1_1") (pintype "passive"))
      (node (ref "SKT1") (pin "22") (pinfunction "PWM1_22") (pintype "bidirectional"))
      (node (ref "SKT1") (pin "P$62") (pinfunction "P$62_P$62") (pintype "bidirectional"))
    )
    (net (code "56") (name "PWM2") (class "Default")
      (node (ref "R13") (pin "1") (pinfunction "P$1_1") (pintype "passive"))
      (node (ref "SKT1") (pin "23") (pinfunction "PWM2_23") (pintype "bidirectional"))
      (node (ref "SKT1") (pin "P$63") (pinfunction "P$63_P$63") (pintype "bidirectional"))
    )
    (net (code "57") (name "RX1") (class "Default")
      (node (ref "CON2") (pin "1") (pinfunction "RX/SCL_1") (pintype "bidirectional"))
      (node (ref "R23") (pin "2") (pinfunction "P$2_2") (pintype "passive"))
      (node (ref "SKT1") (pin "10") (pinfunction "RX1_10") (pintype "bidirectional"))
      (node (ref "SKT1") (pin "P$50") (pinfunction "P$50_P$50") (pintype "bidirectional"))
    )
    (net (code "58") (name "RX2") (class "Default")
      (node (ref "CON6") (pin "1") (pinfunction "RX/SCL_1") (pintype "bidirectional"))
      (node (ref "R18") (pin "2") (pinfunction "P$2_2") (pintype "passive"))
      (node (ref "SKT1") (pin "31") (pinfunction "RX2_31") (pintype "bidirectional"))
      (node (ref "SKT1") (pin "P$71") (pinfunction "P$71_P$71") (pintype "bidirectional"))
    )
    (net (code "59") (name "SCK1") (class "Default")
      (node (ref "CON1") (pin "1") (pinfunction "SCK_1") (pintype "bidirectional"))
      (node (ref "CON10") (pin "5") (pinfunction "SCK_5") (pintype "bidirectional"))
      (node (ref "LCD1") (pin "P$14") (pinfunction "SCL_P$14") (pintype "bidirectional"))
      (node (ref "SKT1") (pin "15") (pinfunction "SCK1_15") (pintype "bidirectional"))
      (node (ref "SKT1") (pin "P$55") (pinfunction "P$55_P$55") (pintype "bidirectional"))
    )
    (net (code "60") (name "SCK2") (class "Default")
      (node (ref "CON7") (pin "1") (pinfunction "SCK_1") (pintype "bidirectional"))
      (node (ref "SKT1") (pin "26") (pinfunction "SCK2_26") (pintype "bidirectional"))
      (node (ref "SKT1") (pin "P$66") (pinfunction "P$66_P$66") (pintype "bidirectional"))
    )
    (net (code "61") (name "SCL") (class "Default")
      (node (ref "IC4") (pin "2") (pinfunction "SCL_2") (pintype "bidirectional"))
      (node (ref "IC5") (pin "6") (pinfunction "SCL_6") (pintype "bidirectional"))
      (node (ref "R15") (pin "1") (pinfunction "P$1_1") (pintype "passive"))
      (node (ref "SJ1") (pin "2") (pinfunction "2_2") (pintype "passive"))
    )
    (net (code "62") (name "SCL1") (class "Default")
      (node (ref "CON5") (pin "1") (pinfunction "RX/SCL_1") (pintype "bidirectional"))
      (node (ref "SJ1") (pin "1") (pinfunction "1_1") (pintype "passive"))
      (node (ref "SKT1") (pin "12") (pinfunction "SCL1_12") (pintype "bidirectional"))
      (node (ref "SKT1") (pin "P$52") (pinfunction "P$52_P$52") (pintype "bidirectional"))
    )
    (net (code "63") (name "SCL2") (class "Default")
      (node (ref "CON8") (pin "1") (pinfunction "RX/SCL_1") (pintype "bidirectional"))
      (node (ref "SJ1") (pin "3") (pinfunction "3_3") (pintype "passive"))
      (node (ref "SKT1") (pin "29") (pinfunction "SCL2_29") (pintype "bidirectional"))
      (node (ref "SKT1") (pin "P$69") (pinfunction "P$69_P$69") (pintype "bidirectional"))
    )
    (net (code "64") (name "SDA") (class "Default")
      (node (ref "IC4") (pin "1") (pinfunction "SDA_1") (pintype "bidirectional"))
      (node (ref "IC5") (pin "5") (pinfunction "SDA_5") (pintype "bidirectional"))
      (node (ref "R14") (pin "1") (pinfunction "P$1_1") (pintype "passive"))
      (node (ref "SJ2") (pin "2") (pinfunction "2_2") (pintype "passive"))
    )
    (net (code "65") (name "SDA1") (class "Default")
      (node (ref "CON5") (pin "2") (pinfunction "TX/SDA_2") (pintype "bidirectional"))
      (node (ref "SJ2") (pin "1") (pinfunction "1_1") (pintype "passive"))
      (node (ref "SKT1") (pin "11") (pinfunction "SDA1_11") (pintype "bidirectional"))
      (node (ref "SKT1") (pin "P$51") (pinfunction "P$51_P$51") (pintype "bidirectional"))
    )
    (net (code "66") (name "SDA2") (class "Default")
      (node (ref "CON8") (pin "2") (pinfunction "TX/SDA_2") (pintype "bidirectional"))
      (node (ref "SJ2") (pin "3") (pinfunction "3_3") (pintype "passive"))
      (node (ref "SKT1") (pin "30") (pinfunction "SDA2_30") (pintype "bidirectional"))
      (node (ref "SKT1") (pin "P$70") (pinfunction "P$70_P$70") (pintype "bidirectional"))
    )
    (net (code "67") (name "TGT_CTS") (class "Default")
      (node (ref "IC3") (pin "30") (pinfunction "PIO0_17/~{RTS}/CT32B0_CAP0/SCLK_30") (pintype "bidirectional"))
      (node (ref "SKT1") (pin "39") (pinfunction "TGT_CTS_39") (pintype "bidirectional"))
      (node (ref "SKT1") (pin "P$79") (pinfunction "P$79_P$79") (pintype "bidirectional"))
    )
    (net (code "68") (name "TGT_NRESET") (class "Default")
      (node (ref "D1") (pin "A") (pinfunction "A_A") (pintype "passive"))
      (node (ref "IC3") (pin "8") (pinfunction "PIO0_2/SSEL0/CT16B0_CAP0_8") (pintype "bidirectional"))
      (node (ref "SKT1") (pin "6") (pinfunction "NRESET_6") (pintype "bidirectional"))
      (node (ref "SKT1") (pin "P$46") (pinfunction "P$46_P$46") (pintype "bidirectional"))
    )
    (net (code "69") (name "TGT_NRESET_BUTTON") (class "Default")
      (node (ref "D1") (pin "K") (pinfunction "K_K") (pintype "passive"))
      (node (ref "R6") (pin "2") (pinfunction "P$2_2") (pintype "passive"))
      (node (ref "R7") (pin "2") (pinfunction "P$2_2") (pintype "passive"))
      (node (ref "SW1") (pin "A1") (pinfunction "A1_A1") (pintype "passive"))
      (node (ref "SW1") (pin "A2") (pinfunction "A2_A2") (pintype "passive"))
    )
    (net (code "70") (name "TGT_NRESET_FB") (class "Default")
      (node (ref "IC3") (pin "3") (pinfunction "PIO0_1/CLKOUT/CT32B0_MAT2/USB_FTOGGLE_3") (pintype "bidirectional"))
      (node (ref "R6") (pin "1") (pinfunction "P$1_1") (pintype "passive"))
    )
    (net (code "71") (name "TGT_NRESET_FB_ISP") (class "Default")
      (node (ref "IC3") (pin "1") (pinfunction "PIO1_19/~{DTR}/SSEL1_1") (pintype "bidirectional"))
      (node (ref "R7") (pin "1") (pinfunction "P$1_1") (pintype "passive"))
    )
    (net (code "72") (name "TGT_RTS") (class "Default")
      (node (ref "IC3") (pin "16") (pinfunction "PIO0_7/~{CTS}_16") (pintype "bidirectional"))
      (node (ref "SKT1") (pin "38") (pinfunction "TGT_RTS_38") (pintype "bidirectional"))
      (node (ref "SKT1") (pin "P$78") (pinfunction "P$78_P$78") (pintype "bidirectional"))
    )
    (net (code "73") (name "TGT_RXD") (class "Default")
      (node (ref "IC3") (pin "32") (pinfunction "PIO0_19/TXD/CT32B0_MAT1_32") (pintype "bidirectional"))
      (node (ref "SKT1") (pin "8") (pinfunction "TGT_RX_8") (pintype "bidirectional"))
      (node (ref "SKT1") (pin "P$48") (pinfunction "P$48_P$48") (pintype "bidirectional"))
    )
    (net (code "74") (name "TGT_SWCLK") (class "Default")
      (node (ref "IC3") (pin "18") (pinfunction "PIO0_9/MOSI0/CT16B0_MAT1_18") (pintype "bidirectional"))
      (node (ref "SKT1") (pin "5") (pinfunction "SWCLK_5") (pintype "bidirectional"))
      (node (ref "SKT1") (pin "P$45") (pinfunction "P$45_P$45") (pintype "bidirectional"))
    )
    (net (code "75") (name "TGT_SWDIO") (class "Default")
      (node (ref "IC3") (pin "17") (pinfunction "PIO0_8/MISO0/CT16B0_MAT0_17") (pintype "bidirectional"))
      (node (ref "SKT1") (pin "4") (pinfunction "SWDIO_4") (pintype "bidirectional"))
      (node (ref "SKT1") (pin "P$44") (pinfunction "P$44_P$44") (pintype "bidirectional"))
    )
    (net (code "76") (name "TGT_TXD") (class "Default")
      (node (ref "IC3") (pin "31") (pinfunction "PIO0_18/RXD/CT32B0_MAT0_31") (pintype "bidirectional"))
      (node (ref "SKT1") (pin "7") (pinfunction "TGT_TX_7") (pintype "bidirectional"))
      (node (ref "SKT1") (pin "P$47") (pinfunction "P$47_P$47") (pintype "bidirectional"))
    )
    (net (code "77") (name "TX1") (class "Default")
      (node (ref "CON2") (pin "2") (pinfunction "TX/SDA_2") (pintype "bidirectional"))
      (node (ref "R23") (pin "1") (pinfunction "P$1_1") (pintype "passive"))
      (node (ref "SKT1") (pin "9") (pinfunction "TX1_9") (pintype "bidirectional"))
      (node (ref "SKT1") (pin "P$49") (pinfunction "P$49_P$49") (pintype "bidirectional"))
    )
    (net (code "78") (name "TX2") (class "Default")
      (node (ref "CON6") (pin "2") (pinfunction "TX/SDA_2") (pintype "bidirectional"))
      (node (ref "R18") (pin "1") (pinfunction "P$1_1") (pintype "passive"))
      (node (ref "SKT1") (pin "32") (pinfunction "TX2_32") (pintype "bidirectional"))
      (node (ref "SKT1") (pin "P$72") (pinfunction "P$72_P$72") (pintype "bidirectional"))
    )
    (net (code "79") (name "USB-D+") (class "Default")
      (node (ref "IC1") (pin "6") (pinfunction "IO1_6") (pintype "bidirectional"))
      (node (ref "R10") (pin "1") (pinfunction "P$1_1") (pintype "passive"))
    )
    (net (code "80") (name "USB-D-") (class "Default")
      (node (ref "IC1") (pin "4") (pinfunction "IO2_4") (pintype "bidirectional"))
      (node (ref "R9") (pin "1") (pinfunction "P$1_1") (pintype "passive"))
    )
    (net (code "81") (name "USB-SCON") (class "Default")
      (node (ref "IC3") (pin "15") (pinfunction "PIO0_6/~{USB_CONNECT}/SCK0_15") (pintype "bidirectional"))
      (node (ref "T1") (pin "1") (pinfunction "G_1") (pintype "passive"))
    )
    (net (code "82") (name "VCC_GROVE") (class "Default")
      (node (ref "CON2") (pin "3") (pinfunction "VCC_3") (pintype "bidirectional"))
      (node (ref "CON3") (pin "3") (pinfunction "VCC_3") (pintype "bidirectional"))
      (node (ref "CON4") (pin "3") (pinfunction "VCC_3") (pintype "bidirectional"))
      (node (ref "CON5") (pin "3") (pinfunction "VCC_3") (pintype "bidirectional"))
      (node (ref "CON6") (pin "3") (pinfunction "VCC_3") (pintype "bidirectional"))
      (node (ref "CON8") (pin "3") (pinfunction "VCC_3") (pintype "bidirectional"))
      (node (ref "JP1") (pin "2") (pinfunction "2_2") (pintype "passive"))
    )
    (net (code "83") (name "unconnected-(CON10-NC-Pad1)") (class "Default")
      (node (ref "CON10") (pin "1") (pinfunction "NC_1") (pintype "bidirectional"))
    )
    (net (code "84") (name "unconnected-(CON10-NC-Pad8)") (class "Default")
      (node (ref "CON10") (pin "8") (pinfunction "NC_8") (pintype "bidirectional"))
    )
    (net (code "85") (name "unconnected-(CON10-PadCD)") (class "Default")
      (node (ref "CON10") (pin "CD") (pinfunction "CD_CD") (pintype "bidirectional"))
    )
    (net (code "86") (name "unconnected-(IC3-PIO0_4{slash}SCL-Pad10)") (class "Default")
      (node (ref "IC3") (pin "10") (pinfunction "PIO0_4/SCL_10") (pintype "bidirectional"))
    )
    (net (code "87") (name "unconnected-(IC3-PIO0_5{slash}SDA-Pad11)") (class "Default")
      (node (ref "IC3") (pin "11") (pinfunction "PIO0_5/SDA_11") (pintype "bidirectional"))
    )
    (net (code "88") (name "unconnected-(IC3-PIO0_16{slash}AD5{slash}CT32B1_MAT3{slash}WAKEUP-Pad26)") (class "Default")
      (node (ref "IC3") (pin "26") (pinfunction "PIO0_16/AD5/CT32B1_MAT3/WAKEUP_26") (pintype "bidirectional"))
    )
    (net (code "89") (name "unconnected-(IC3-PIO0_22{slash}AD6{slash}CT16B1_MAT1{slash}MISO1-Pad20)") (class "Default")
      (node (ref "IC3") (pin "20") (pinfunction "PIO0_22/AD6/CT16B1_MAT1/MISO1_20") (pintype "bidirectional"))
    )
    (net (code "90") (name "unconnected-(IC3-PIO0_23{slash}AD7-Pad27)") (class "Default")
      (node (ref "IC3") (pin "27") (pinfunction "PIO0_23/AD7_27") (pintype "bidirectional"))
    )
    (net (code "91") (name "unconnected-(IC3-PIO1_15{slash}~{DCD}{slash}CT16B0_MAT2{slash}SCK1-Pad28)") (class "Default")
      (node (ref "IC3") (pin "28") (pinfunction "PIO1_15/~{DCD}/CT16B0_MAT2/SCK1_28") (pintype "bidirectional"))
    )
    (net (code "92") (name "unconnected-(IC3-TDO{slash}PIO0_13{slash}AD2{slash}CT32B1_MAT0-Pad23)") (class "Default")
      (node (ref "IC3") (pin "23") (pinfunction "TDO/PIO0_13/AD2/CT32B1_MAT0_23") (pintype "bidirectional"))
    )
    (net (code "93") (name "unconnected-(IC3-TMS{slash}PIO0_12{slash}AD1{slash}CT32B1_CAP0-Pad22)") (class "Default")
      (node (ref "IC3") (pin "22") (pinfunction "TMS/PIO0_12/AD1/CT32B1_CAP0_22") (pintype "bidirectional"))
    )
    (net (code "94") (name "unconnected-(IC3-~{TRST}{slash}PIO0_14{slash}AD3{slash}CT32B1_MAT1-Pad24)") (class "Default")
      (node (ref "IC3") (pin "24") (pinfunction "~{TRST}/PIO0_14/AD3/CT32B1_MAT1_24") (pintype "bidirectional"))
    )
    (net (code "95") (name "unconnected-(IC4-OS-Pad3)") (class "Default")
      (node (ref "IC4") (pin "3") (pinfunction "OS_3") (pintype "bidirectional"))
    )
    (net (code "96") (name "unconnected-(IC5-WP-Pad7)") (class "Default")
      (node (ref "IC5") (pin "7") (pinfunction "WP_7") (pintype "bidirectional"))
    )
    (net (code "97") (name "unconnected-(SW3-Pad1)") (class "Default")
      (node (ref "SW3") (pin "1") (pinfunction "1_1") (pintype "bidirectional"))
    )
    (net (code "98") (name "unconnected-(SW3-Pad5)") (class "Default")
      (node (ref "SW3") (pin "5") (pinfunction "5_5") (pintype "bidirectional"))
    )
    (net (code "99") (name "unconnected-(SW3-Pad6)") (class "Default")
      (node (ref "SW3") (pin "6") (pinfunction "6_6") (pintype "bidirectional"))
    )
    (net (code "100") (name "unconnected-(SW3-Pad7)") (class "Default")
      (node (ref "SW3") (pin "7") (pinfunction "7_7") (pintype "bidirectional"))
    )
  )
)
